# stm32-lqfp64-adapter.net
KiCad netlist of a schematic drawn in EAGLE
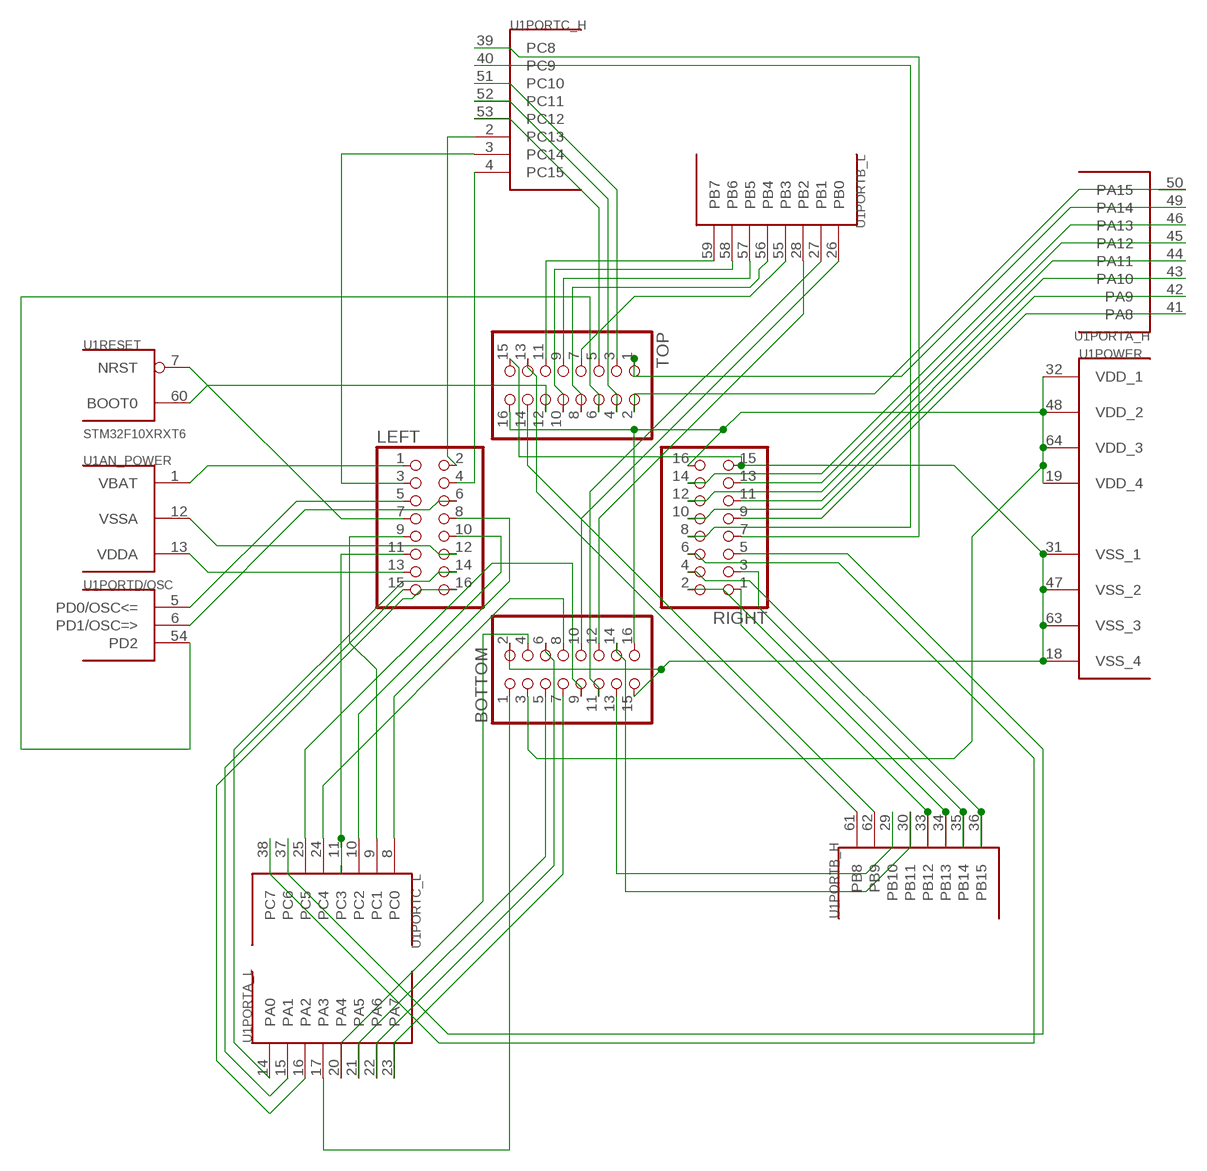
[diagram p0: schematic, sheet 1]

(export (version "E")
  (design (tool "Eeschema 10.0.6"))
  (components
    (comp (ref "BOTTOM")
      (value "PINHD-2X08_2.54")
      (footprint "eagle-import:2X08")
      (libsource (lib "eagle-import") (part "PINHD-2X08_2.54"))
    )
    (comp (ref "LEFT")
      (value "PINHD-2X08_2.54")
      (footprint "eagle-import:2X08")
      (libsource (lib "eagle-import") (part "PINHD-2X08_2.54"))
    )
    (comp (ref "RIGHT")
      (value "PINHD-2X08_2.54")
      (footprint "eagle-import:2X08")
      (libsource (lib "eagle-import") (part "PINHD-2X08_2.54"))
    )
    (comp (ref "TOP")
      (value "PINHD-2X08_2.54")
      (footprint "eagle-import:2X08")
      (libsource (lib "eagle-import") (part "PINHD-2X08_2.54"))
    )
    (comp (ref "U1")
      (value "STM32F10XRXT6")
      (footprint "eagle-import:TQFP64")
      (libsource (lib "eagle-import") (part "STM32F10XRXT6"))
    )
  )
  (nets
    (net (code "1") (name "Net-(U1A-VBAT)") (class "Default")
      (node (ref "LEFT") (pin "1") (pinfunction "1_1") (pintype "passive"))
      (node (ref "U1") (pin "1") (pinfunction "VBAT_1") (pintype "power_in"))
    )
    (net (code "2") (name "Net-(U1A-VDDA)") (class "Default")
      (node (ref "LEFT") (pin "13") (pinfunction "13_13") (pintype "passive"))
      (node (ref "U1") (pin "13") (pinfunction "VDDA_13") (pintype "power_in"))
    )
    (net (code "3") (name "Net-(U1A-VSSA)") (class "Default")
      (node (ref "LEFT") (pin "12") (pinfunction "12_12") (pintype "passive"))
      (node (ref "U1") (pin "12") (pinfunction "VSSA_12") (pintype "power_in"))
    )
    (net (code "4") (name "Net-(U1B-PA8)") (class "Default")
      (node (ref "RIGHT") (pin "9") (pinfunction "9_9") (pintype "passive"))
      (node (ref "U1") (pin "41") (pinfunction "PA8_41") (pintype "bidirectional"))
    )
    (net (code "5") (name "Net-(U1B-PA9)") (class "Default")
      (node (ref "RIGHT") (pin "10") (pinfunction "10_10") (pintype "passive"))
      (node (ref "U1") (pin "42") (pinfunction "PA9_42") (pintype "bidirectional"))
    )
    (net (code "6") (name "Net-(U1B-PA10)") (class "Default")
      (node (ref "RIGHT") (pin "11") (pinfunction "11_11") (pintype "passive"))
      (node (ref "U1") (pin "43") (pinfunction "PA10_43") (pintype "bidirectional"))
    )
    (net (code "7") (name "Net-(U1B-PA11)") (class "Default")
      (node (ref "RIGHT") (pin "12") (pinfunction "12_12") (pintype "passive"))
      (node (ref "U1") (pin "44") (pinfunction "PA11_44") (pintype "bidirectional"))
    )
    (net (code "8") (name "Net-(U1B-PA12)") (class "Default")
      (node (ref "RIGHT") (pin "13") (pinfunction "13_13") (pintype "passive"))
      (node (ref "U1") (pin "45") (pinfunction "PA12_45") (pintype "bidirectional"))
    )
    (net (code "9") (name "Net-(U1B-PA13)") (class "Default")
      (node (ref "RIGHT") (pin "14") (pinfunction "14_14") (pintype "passive"))
      (node (ref "U1") (pin "46") (pinfunction "PA13_46") (pintype "bidirectional"))
    )
    (net (code "10") (name "Net-(U1B-PA14)") (class "Default")
      (node (ref "TOP") (pin "1") (pinfunction "1_1") (pintype "passive"))
      (node (ref "U1") (pin "49") (pinfunction "PA14_49") (pintype "bidirectional"))
    )
    (net (code "11") (name "Net-(U1B-PA15)") (class "Default")
      (node (ref "TOP") (pin "2") (pinfunction "2_2") (pintype "passive"))
      (node (ref "U1") (pin "50") (pinfunction "PA15_50") (pintype "bidirectional"))
    )
    (net (code "12") (name "Net-(U1C-PA0)") (class "Default")
      (node (ref "LEFT") (pin "14") (pinfunction "14_14") (pintype "passive"))
      (node (ref "U1") (pin "14") (pinfunction "PA0_14") (pintype "bidirectional"))
    )
    (net (code "13") (name "Net-(U1C-PA1)") (class "Default")
      (node (ref "LEFT") (pin "15") (pinfunction "15_15") (pintype "passive"))
      (node (ref "U1") (pin "15") (pinfunction "PA1_15") (pintype "bidirectional"))
    )
    (net (code "14") (name "Net-(U1C-PA2)") (class "Default")
      (node (ref "LEFT") (pin "16") (pinfunction "16_16") (pintype "passive"))
      (node (ref "U1") (pin "16") (pinfunction "PA2_16") (pintype "bidirectional"))
    )
    (net (code "15") (name "Net-(U1C-PA3)") (class "Default")
      (node (ref "BOTTOM") (pin "1") (pinfunction "1_1") (pintype "passive"))
      (node (ref "U1") (pin "17") (pinfunction "PA3_17") (pintype "bidirectional"))
    )
    (net (code "16") (name "Net-(U1C-PA4)") (class "Default")
      (node (ref "BOTTOM") (pin "4") (pinfunction "4_4") (pintype "passive"))
      (node (ref "U1") (pin "20") (pinfunction "PA4_20") (pintype "bidirectional"))
    )
    (net (code "17") (name "Net-(U1C-PA5)") (class "Default")
      (node (ref "BOTTOM") (pin "5") (pinfunction "5_5") (pintype "passive"))
      (node (ref "U1") (pin "21") (pinfunction "PA5_21") (pintype "bidirectional"))
    )
    (net (code "18") (name "Net-(U1C-PA6)") (class "Default")
      (node (ref "BOTTOM") (pin "6") (pinfunction "6_6") (pintype "passive"))
      (node (ref "U1") (pin "22") (pinfunction "PA6_22") (pintype "bidirectional"))
    )
    (net (code "19") (name "Net-(U1C-PA7)") (class "Default")
      (node (ref "BOTTOM") (pin "7") (pinfunction "7_7") (pintype "passive"))
      (node (ref "U1") (pin "23") (pinfunction "PA7_23") (pintype "bidirectional"))
    )
    (net (code "20") (name "Net-(U1D-PB8)") (class "Default")
      (node (ref "TOP") (pin "13") (pinfunction "13_13") (pintype "passive"))
      (node (ref "U1") (pin "61") (pinfunction "PB8_61") (pintype "bidirectional"))
    )
    (net (code "21") (name "Net-(U1D-PB9)") (class "Default")
      (node (ref "TOP") (pin "14") (pinfunction "14_14") (pintype "passive"))
      (node (ref "U1") (pin "62") (pinfunction "PB9_62") (pintype "bidirectional"))
    )
    (net (code "22") (name "Net-(U1D-PB10)") (class "Default")
      (node (ref "BOTTOM") (pin "13") (pinfunction "13_13") (pintype "passive"))
      (node (ref "U1") (pin "29") (pinfunction "PB10_29") (pintype "bidirectional"))
    )
    (net (code "23") (name "Net-(U1D-PB11)") (class "Default")
      (node (ref "BOTTOM") (pin "14") (pinfunction "14_14") (pintype "passive"))
      (node (ref "U1") (pin "30") (pinfunction "PB11_30") (pintype "bidirectional"))
    )
    (net (code "24") (name "Net-(U1D-PB12)") (class "Default")
      (node (ref "RIGHT") (pin "1") (pinfunction "1_1") (pintype "passive"))
      (node (ref "U1") (pin "33") (pinfunction "PB12_33") (pintype "bidirectional"))
    )
    (net (code "25") (name "Net-(U1D-PB13)") (class "Default")
      (node (ref "RIGHT") (pin "2") (pinfunction "2_2") (pintype "passive"))
      (node (ref "U1") (pin "34") (pinfunction "PB13_34") (pintype "bidirectional"))
    )
    (net (code "26") (name "Net-(U1D-PB14)") (class "Default")
      (node (ref "RIGHT") (pin "3") (pinfunction "3_3") (pintype "passive"))
      (node (ref "U1") (pin "35") (pinfunction "PB14_35") (pintype "bidirectional"))
    )
    (net (code "27") (name "Net-(U1D-PB15)") (class "Default")
      (node (ref "RIGHT") (pin "4") (pinfunction "4_4") (pintype "passive"))
      (node (ref "U1") (pin "36") (pinfunction "PB15_36") (pintype "bidirectional"))
    )
    (net (code "28") (name "Net-(U1E-PB0)") (class "Default")
      (node (ref "BOTTOM") (pin "10") (pinfunction "10_10") (pintype "passive"))
      (node (ref "U1") (pin "26") (pinfunction "PB0_26") (pintype "bidirectional"))
    )
    (net (code "29") (name "Net-(U1E-PB1)") (class "Default")
      (node (ref "BOTTOM") (pin "11") (pinfunction "11_11") (pintype "passive"))
      (node (ref "U1") (pin "27") (pinfunction "PB1_27") (pintype "bidirectional"))
    )
    (net (code "30") (name "Net-(U1E-PB2)") (class "Default")
      (node (ref "BOTTOM") (pin "12") (pinfunction "12_12") (pintype "passive"))
      (node (ref "U1") (pin "28") (pinfunction "PB2_28") (pintype "bidirectional"))
    )
    (net (code "31") (name "Net-(U1E-PB3)") (class "Default")
      (node (ref "TOP") (pin "7") (pinfunction "7_7") (pintype "passive"))
      (node (ref "U1") (pin "55") (pinfunction "PB3_55") (pintype "bidirectional"))
    )
    (net (code "32") (name "Net-(U1E-PB4)") (class "Default")
      (node (ref "TOP") (pin "8") (pinfunction "8_8") (pintype "passive"))
      (node (ref "U1") (pin "56") (pinfunction "PB4_56") (pintype "bidirectional"))
    )
    (net (code "33") (name "Net-(U1E-PB5)") (class "Default")
      (node (ref "TOP") (pin "9") (pinfunction "9_9") (pintype "passive"))
      (node (ref "U1") (pin "57") (pinfunction "PB5_57") (pintype "bidirectional"))
    )
    (net (code "34") (name "Net-(U1E-PB6)") (class "Default")
      (node (ref "TOP") (pin "10") (pinfunction "10_10") (pintype "passive"))
      (node (ref "U1") (pin "58") (pinfunction "PB6_58") (pintype "bidirectional"))
    )
    (net (code "35") (name "Net-(U1E-PB7)") (class "Default")
      (node (ref "TOP") (pin "11") (pinfunction "11_11") (pintype "passive"))
      (node (ref "U1") (pin "59") (pinfunction "PB7_59") (pintype "bidirectional"))
    )
    (net (code "36") (name "Net-(U1F-PC8)") (class "Default")
      (node (ref "RIGHT") (pin "7") (pinfunction "7_7") (pintype "passive"))
      (node (ref "U1") (pin "39") (pinfunction "PC8_39") (pintype "bidirectional"))
    )
    (net (code "37") (name "Net-(U1F-PC9)") (class "Default")
      (node (ref "RIGHT") (pin "8") (pinfunction "8_8") (pintype "passive"))
      (node (ref "U1") (pin "40") (pinfunction "PC9_40") (pintype "bidirectional"))
    )
    (net (code "38") (name "Net-(U1F-PC10)") (class "Default")
      (node (ref "TOP") (pin "3") (pinfunction "3_3") (pintype "passive"))
      (node (ref "U1") (pin "51") (pinfunction "PC10_51") (pintype "bidirectional"))
    )
    (net (code "39") (name "Net-(U1F-PC11)") (class "Default")
      (node (ref "TOP") (pin "4") (pinfunction "4_4") (pintype "passive"))
      (node (ref "U1") (pin "52") (pinfunction "PC11_52") (pintype "bidirectional"))
    )
    (net (code "40") (name "Net-(U1F-PC12)") (class "Default")
      (node (ref "TOP") (pin "5") (pinfunction "5_5") (pintype "passive"))
      (node (ref "U1") (pin "53") (pinfunction "PC12_53") (pintype "bidirectional"))
    )
    (net (code "41") (name "Net-(U1F-PC13)") (class "Default")
      (node (ref "LEFT") (pin "2") (pinfunction "2_2") (pintype "passive"))
      (node (ref "U1") (pin "2") (pinfunction "PC13_2") (pintype "bidirectional"))
    )
    (net (code "42") (name "Net-(U1F-PC14)") (class "Default")
      (node (ref "LEFT") (pin "3") (pinfunction "3_3") (pintype "passive"))
      (node (ref "U1") (pin "3") (pinfunction "PC14_3") (pintype "bidirectional"))
    )
    (net (code "43") (name "Net-(U1F-PC15)") (class "Default")
      (node (ref "LEFT") (pin "4") (pinfunction "4_4") (pintype "passive"))
      (node (ref "U1") (pin "4") (pinfunction "PC15_4") (pintype "bidirectional"))
    )
    (net (code "44") (name "Net-(U1G-PC0)") (class "Default")
      (node (ref "LEFT") (pin "8") (pinfunction "8_8") (pintype "passive"))
      (node (ref "U1") (pin "8") (pinfunction "PC0_8") (pintype "bidirectional"))
    )
    (net (code "45") (name "Net-(U1G-PC1)") (class "Default")
      (node (ref "LEFT") (pin "9") (pinfunction "9_9") (pintype "passive"))
      (node (ref "U1") (pin "9") (pinfunction "PC1_9") (pintype "bidirectional"))
    )
    (net (code "46") (name "Net-(U1G-PC2)") (class "Default")
      (node (ref "LEFT") (pin "10") (pinfunction "10_10") (pintype "passive"))
      (node (ref "U1") (pin "10") (pinfunction "PC2_10") (pintype "bidirectional"))
    )
    (net (code "47") (name "Net-(U1G-PC3)") (class "Default")
      (node (ref "LEFT") (pin "11") (pinfunction "11_11") (pintype "passive"))
      (node (ref "U1") (pin "11") (pinfunction "PC3_11") (pintype "bidirectional"))
    )
    (net (code "48") (name "Net-(U1G-PC4)") (class "Default")
      (node (ref "BOTTOM") (pin "8") (pinfunction "8_8") (pintype "passive"))
      (node (ref "U1") (pin "24") (pinfunction "PC4_24") (pintype "bidirectional"))
    )
    (net (code "49") (name "Net-(U1G-PC5)") (class "Default")
      (node (ref "BOTTOM") (pin "9") (pinfunction "9_9") (pintype "passive"))
      (node (ref "U1") (pin "25") (pinfunction "PC5_25") (pintype "bidirectional"))
    )
    (net (code "50") (name "Net-(U1G-PC6)") (class "Default")
      (node (ref "RIGHT") (pin "5") (pinfunction "5_5") (pintype "passive"))
      (node (ref "U1") (pin "37") (pinfunction "PC6_37") (pintype "bidirectional"))
    )
    (net (code "51") (name "Net-(U1G-PC7)") (class "Default")
      (node (ref "RIGHT") (pin "6") (pinfunction "6_6") (pintype "passive"))
      (node (ref "U1") (pin "38") (pinfunction "PC7_38") (pintype "bidirectional"))
    )
    (net (code "52") (name "Net-(U1H-PD0{slash}OSC<=)") (class "Default")
      (node (ref "LEFT") (pin "5") (pinfunction "5_5") (pintype "passive"))
      (node (ref "U1") (pin "5") (pinfunction "PD0/OSC<=_5") (pintype "bidirectional"))
    )
    (net (code "53") (name "Net-(U1H-PD1{slash}OSC=>)") (class "Default")
      (node (ref "LEFT") (pin "6") (pinfunction "6_6") (pintype "passive"))
      (node (ref "U1") (pin "6") (pinfunction "PD1/OSC=>_6") (pintype "bidirectional"))
    )
    (net (code "54") (name "Net-(U1H-PD2)") (class "Default")
      (node (ref "TOP") (pin "6") (pinfunction "6_6") (pintype "passive"))
      (node (ref "U1") (pin "54") (pinfunction "PD2_54") (pintype "bidirectional"))
    )
    (net (code "55") (name "Net-(U1I-VDD_1)") (class "Default")
      (node (ref "BOTTOM") (pin "16") (pinfunction "16_16") (pintype "passive"))
      (node (ref "BOTTOM") (pin "3") (pinfunction "3_3") (pintype "passive"))
      (node (ref "RIGHT") (pin "16") (pinfunction "16_16") (pintype "passive"))
      (node (ref "TOP") (pin "16") (pinfunction "16_16") (pintype "passive"))
      (node (ref "U1") (pin "19") (pinfunction "VDD_4_19") (pintype "power_in"))
      (node (ref "U1") (pin "32") (pinfunction "VDD_1_32") (pintype "power_in"))
      (node (ref "U1") (pin "48") (pinfunction "VDD_2_48") (pintype "power_in"))
      (node (ref "U1") (pin "64") (pinfunction "VDD_3_64") (pintype "power_in"))
    )
    (net (code "56") (name "Net-(U1I-VSS_1)") (class "Default")
      (node (ref "BOTTOM") (pin "15") (pinfunction "15_15") (pintype "passive"))
      (node (ref "BOTTOM") (pin "2") (pinfunction "2_2") (pintype "passive"))
      (node (ref "RIGHT") (pin "15") (pinfunction "15_15") (pintype "passive"))
      (node (ref "TOP") (pin "15") (pinfunction "15_15") (pintype "passive"))
      (node (ref "U1") (pin "18") (pinfunction "VSS_4_18") (pintype "power_in"))
      (node (ref "U1") (pin "31") (pinfunction "VSS_1_31") (pintype "power_in"))
      (node (ref "U1") (pin "47") (pinfunction "VSS_2_47") (pintype "power_in"))
      (node (ref "U1") (pin "63") (pinfunction "VSS_3_63") (pintype "power_in"))
    )
    (net (code "57") (name "Net-(U1J-BOOT0)") (class "Default")
      (node (ref "TOP") (pin "12") (pinfunction "12_12") (pintype "passive"))
      (node (ref "U1") (pin "60") (pinfunction "BOOT0_60") (pintype "input"))
    )
    (net (code "58") (name "Net-(U1J-NRST)") (class "Default")
      (node (ref "LEFT") (pin "7") (pinfunction "7_7") (pintype "passive"))
      (node (ref "U1") (pin "7") (pinfunction "NRST_7") (pintype "input"))
    )
  )
)
